# HC-SR04_v2_SCH.net
KiCad netlist of a schematic drawn in Altium Designer
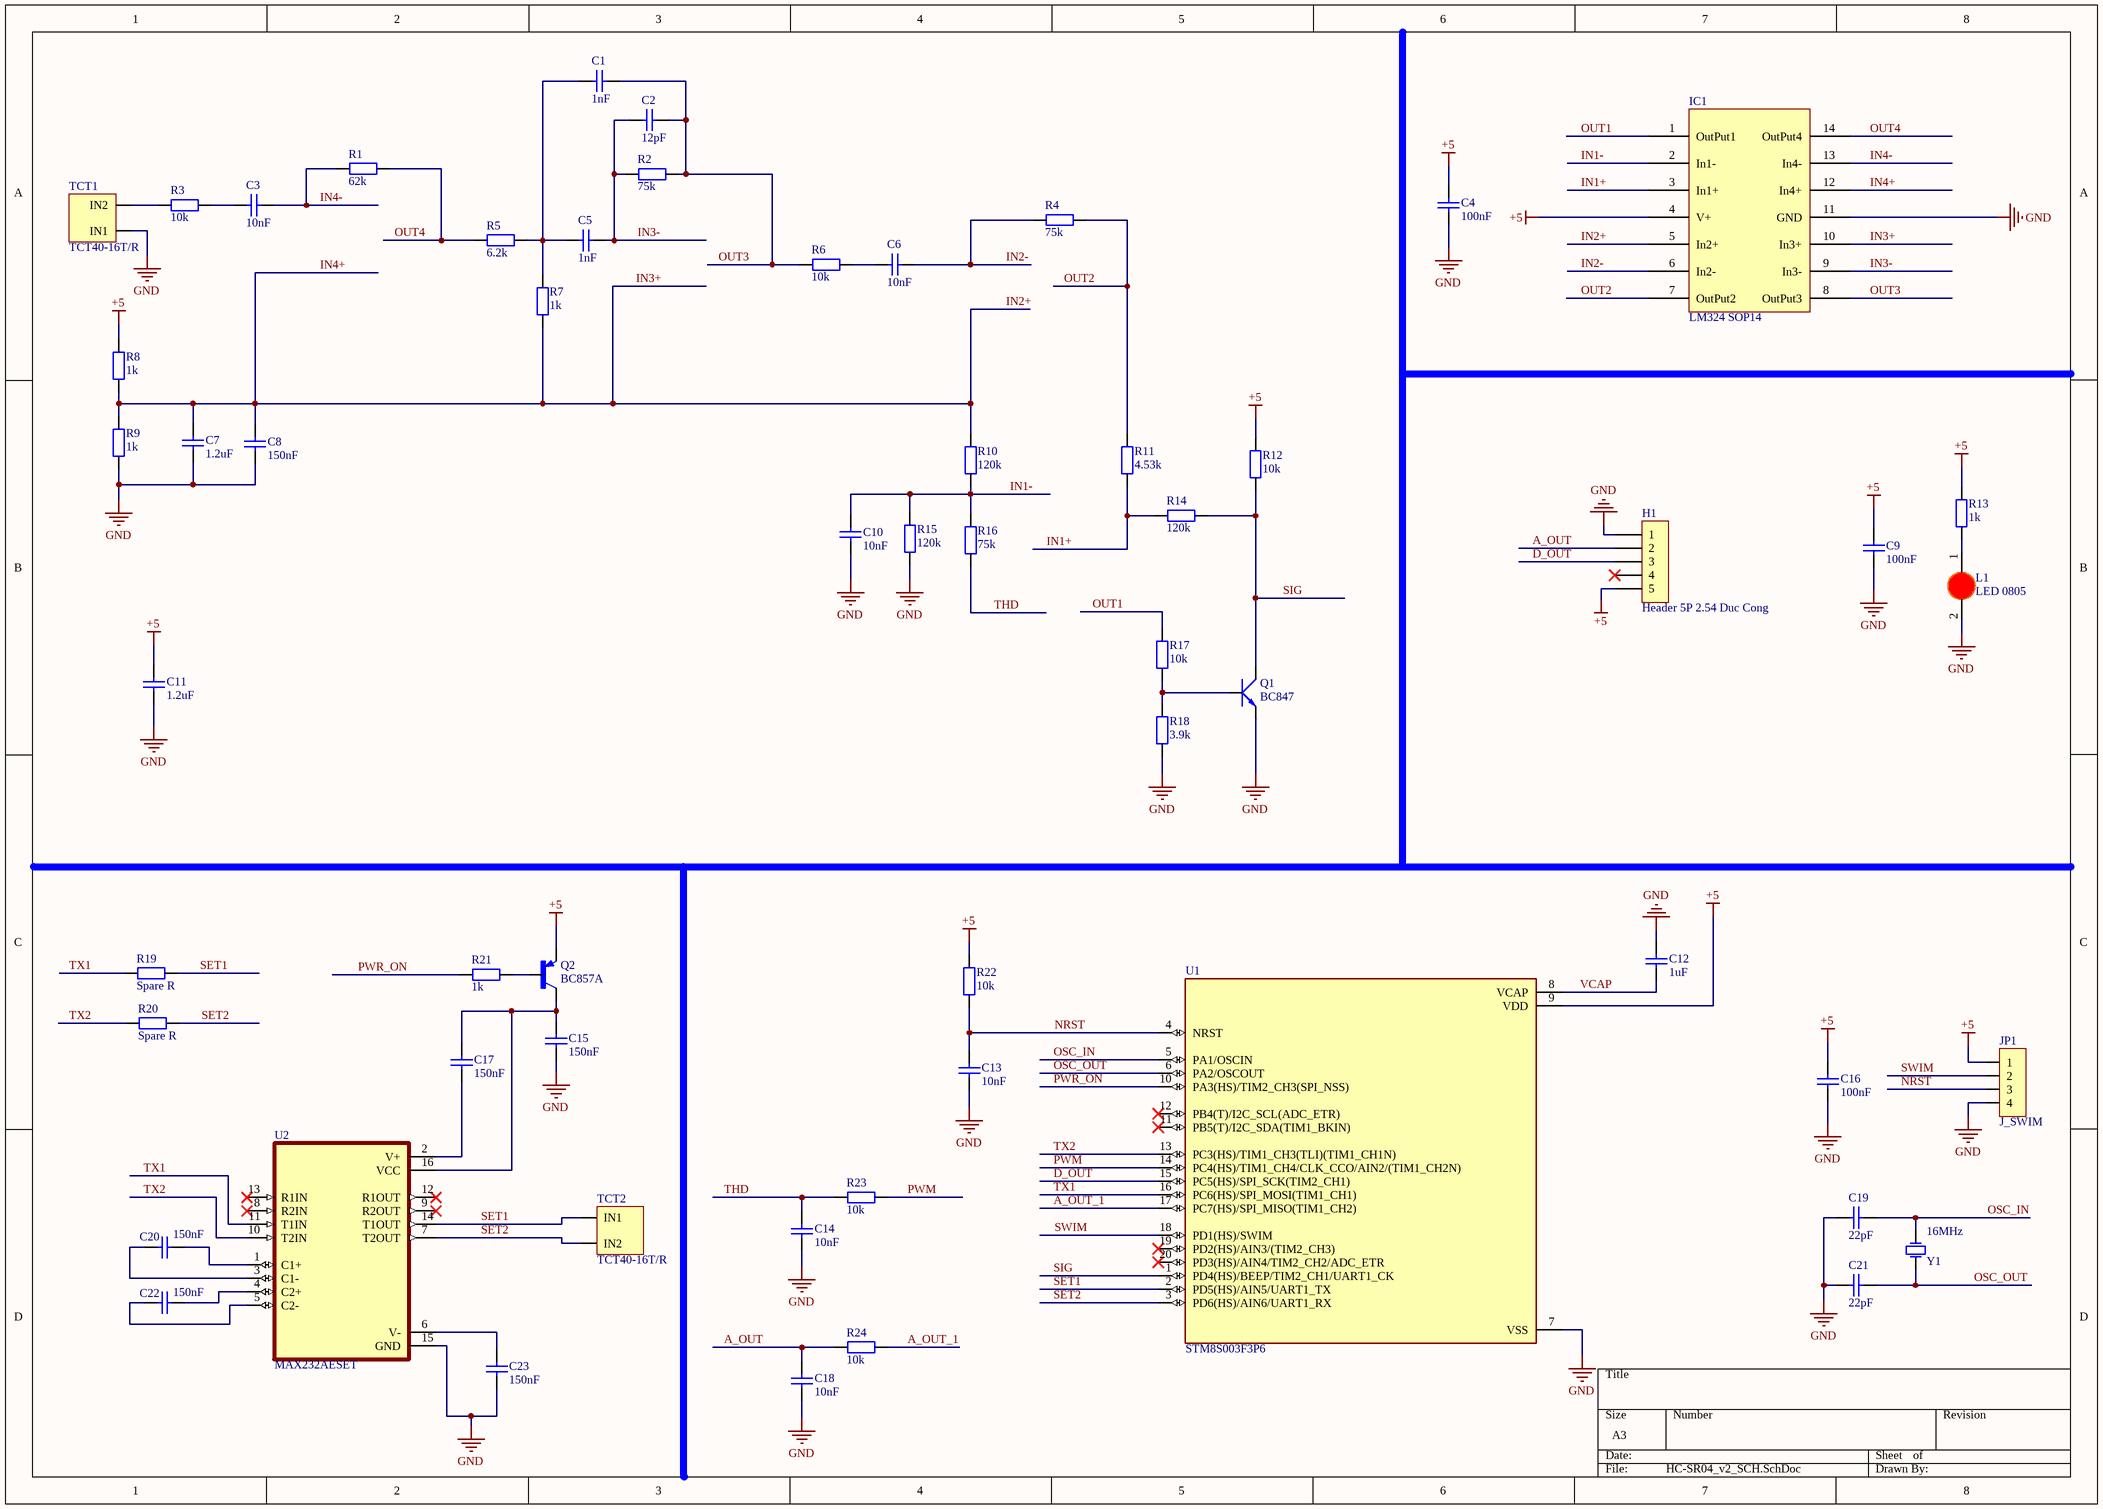
[diagram p0: HC-SR04_v2_SCH.SchDoc]

(export (version "E")
  (design (tool "Eeschema 10.0.6"))
  (components
    (comp (ref "C1")
      (value "1nF")
      (footprint "tu 0603")
      (description "Dán")
      (libsource (lib "namnt_Lib") (part "Tu 0603 102 50V 10%"))
    )
    (comp (ref "C2")
      (value "12pF")
      (footprint "tu 0603")
      (description "Dán")
      (libsource (lib "namnt_Lib") (part "Tu 0603 102 50V 10%"))
    )
    (comp (ref "C3")
      (value "10nF")
      (footprint "tu 0603")
      (description "Dán")
      (libsource (lib "namnt_Lib") (part "Tu 0603 103 50V 10%"))
    )
    (comp (ref "C4")
      (value "100nF")
      (footprint "tu 0603")
      (description "Dán")
      (libsource (lib "namnt_Lib") (part "Tu 0603 102 50V 10%"))
    )
    (comp (ref "C5")
      (value "1nF")
      (footprint "tu 0603")
      (description "Dán")
      (libsource (lib "namnt_Lib") (part "Tu 0603 102 50V 10%"))
    )
    (comp (ref "C6")
      (value "10nF")
      (footprint "tu 0603")
      (description "Dán")
      (libsource (lib "namnt_Lib") (part "Tu 0603 102 50V 10%"))
    )
    (comp (ref "C7")
      (value "1.2uF")
      (footprint "tu 0603")
      (description "Dán")
      (libsource (lib "namnt_Lib") (part "Tu 0603 104 50V 10%"))
    )
    (comp (ref "C8")
      (value "150nF")
      (footprint "tu 0603")
      (description "Dán")
      (libsource (lib "namnt_Lib") (part "Tu 0603 104 50V 10%"))
    )
    (comp (ref "C9")
      (value "100nF")
      (footprint "tu 0603")
      (description "Dán")
      (libsource (lib "namnt_Lib") (part "Tu 0603 102 50V 10%"))
    )
    (comp (ref "C10")
      (value "10nF")
      (footprint "tu 0603")
      (description "Dán")
      (libsource (lib "namnt_Lib") (part "Tu 0603 102 50V 10%"))
    )
    (comp (ref "C11")
      (value "1.2uF")
      (footprint "tu 0603")
      (description "Dán")
      (libsource (lib "namnt_Lib") (part "Tu 0603 102 50V 10%"))
    )
    (comp (ref "C12")
      (value "1uF")
      (footprint "tu 0603")
      (description "Dán")
      (libsource (lib "namnt_Lib") (part "Tu 0603 102 50V 10%"))
    )
    (comp (ref "C13")
      (value "10nF")
      (footprint "tu 0603")
      (description "Dán")
      (libsource (lib "namnt_Lib") (part "Tu 0603 102 50V 10%"))
    )
    (comp (ref "C14")
      (value "10nF")
      (footprint "tu 0603")
      (description "Dán")
      (libsource (lib "namnt_Lib") (part "Tu 0603 102 50V 10%"))
    )
    (comp (ref "C15")
      (value "150nF")
      (footprint "tu 0603")
      (description "Dán")
      (libsource (lib "namnt_Lib") (part "Tu 0603 102 50V 10%"))
    )
    (comp (ref "C16")
      (value "100nF")
      (footprint "tu 0603")
      (description "Dán")
      (libsource (lib "namnt_Lib") (part "Tu 0603 102 50V 10%"))
    )
    (comp (ref "C17")
      (value "150nF")
      (footprint "tu 0603")
      (description "Dán")
      (libsource (lib "namnt_Lib") (part "Tu 0603 102 50V 10%"))
    )
    (comp (ref "C18")
      (value "10nF")
      (footprint "tu 0603")
      (description "Dán")
      (libsource (lib "namnt_Lib") (part "Tu 0603 102 50V 10%"))
    )
    (comp (ref "C19")
      (value "22pF")
      (footprint "tu 0603")
      (description "Dán")
      (libsource (lib "namnt_Lib") (part "Tu 0603 102 50V 10%"))
    )
    (comp (ref "C20")
      (value "150nF")
      (footprint "tu 0603")
      (description "Dán")
      (libsource (lib "namnt_Lib") (part "Tu 0603 102 50V 10%"))
    )
    (comp (ref "C21")
      (value "22pF")
      (footprint "tu 0603")
      (description "Dán")
      (libsource (lib "namnt_Lib") (part "Tu 0603 102 50V 10%"))
    )
    (comp (ref "C22")
      (value "150nF")
      (footprint "tu 0603")
      (description "Dán")
      (libsource (lib "namnt_Lib") (part "Tu 0603 102 50V 10%"))
    )
    (comp (ref "C23")
      (value "150nF")
      (footprint "tu 0603")
      (description "Dán")
      (libsource (lib "namnt_Lib") (part "Tu 0603 102 50V 10%"))
    )
    (comp (ref "H1")
      (value "Header 5P 2.54 Duc Cong")
      (footprint "Header 5P DC 2.54")
      (description "Cắm")
      (libsource (lib "namnt_Lib") (part "Header 5P 2.54 Duc Cong"))
    )
    (comp (ref "IC1")
      (value "LM324 SOP14")
      (footprint "sop 14")
      (description "Dán")
      (libsource (lib "namnt_Lib") (part "LM324 SOP14"))
    )
    (comp (ref "JP1")
      (value "J_SWIM")
      (footprint "JP 1x4 DT")
      (description "Cắm")
      (libsource (lib "namnt_Lib") (part "JP 1x4 2.54 Duc Thang"))
    )
    (comp (ref "L1")
      (value "LED 0805")
      (footprint "LED-0805-Red")
      (description "Dán")
      (libsource (lib "namnt_Lib") (part "LED 0805 Do"))
    )
    (comp (ref "Q1")
      (value "BC847")
      (footprint "SOT-23")
      (description "SOT-23")
      (libsource (lib "namnt_Lib") (part "Trans BC817"))
    )
    (comp (ref "Q2")
      (value "BC857A")
      (footprint "TRANS_BC857A_RFG")
      (description "SOT-23, 200mW, PNP Bipolar Transistor")
      (fields (field (name "MF") "Taiwan Semiconductor") (field (name "MP") "BC857A RFG"))
      (libsource (lib "namnt_Lib") (part "BC857A_RFG"))
    )
    (comp (ref "R1")
      (value "62k")
      (footprint "tro smd 0603")
      (description "Dán")
      (libsource (lib "namnt_Lib") (part "Tro 0603 1% 1k"))
    )
    (comp (ref "R2")
      (value "75k")
      (footprint "tro smd 0603")
      (description "Dán")
      (libsource (lib "namnt_Lib") (part "Tro 0603 1% 1k"))
    )
    (comp (ref "R3")
      (value "10k")
      (footprint "tro smd 0603")
      (description "Dán")
      (libsource (lib "namnt_Lib") (part "Tro 0603 1% 10k"))
    )
    (comp (ref "R4")
      (value "75k")
      (footprint "tro smd 0603")
      (description "Dán")
      (libsource (lib "namnt_Lib") (part "Tro 0603 1% 1k"))
    )
    (comp (ref "R5")
      (value "6.2k")
      (footprint "tro smd 0603")
      (description "Dán")
      (libsource (lib "namnt_Lib") (part "Tro 0603 1% 1k"))
    )
    (comp (ref "R6")
      (value "10k")
      (footprint "tro smd 0603")
      (description "Dán")
      (libsource (lib "namnt_Lib") (part "Tro 0603 1% 1k"))
    )
    (comp (ref "R7")
      (value "1k")
      (footprint "tro smd 0603")
      (description "Dán")
      (libsource (lib "namnt_Lib") (part "Tro 0603 1% 1k"))
    )
    (comp (ref "R8")
      (value "1k")
      (footprint "tro smd 0603")
      (description "Dán")
      (libsource (lib "namnt_Lib") (part "Tro 0603 1% 1k"))
    )
    (comp (ref "R9")
      (value "1k")
      (footprint "tro smd 0603")
      (description "Dán")
      (libsource (lib "namnt_Lib") (part "Tro 0603 1% 1k"))
    )
    (comp (ref "R10")
      (value "120k")
      (footprint "tro smd 0603")
      (description "Dán")
      (libsource (lib "namnt_Lib") (part "Tro 0603 1% 1k"))
    )
    (comp (ref "R11")
      (value "4.53k")
      (footprint "tro smd 0603")
      (description "Dán")
      (libsource (lib "namnt_Lib") (part "Tro 0603 1% 1k"))
    )
    (comp (ref "R12")
      (value "10k")
      (footprint "tro smd 0603")
      (description "Dán")
      (libsource (lib "namnt_Lib") (part "Tro 0603 1% 1k"))
    )
    (comp (ref "R13")
      (value "1k")
      (footprint "tro smd 0603")
      (description "Dán")
      (libsource (lib "namnt_Lib") (part "Tro 0603 1% 1k"))
    )
    (comp (ref "R14")
      (value "120k")
      (footprint "tro smd 0603")
      (description "Dán")
      (libsource (lib "namnt_Lib") (part "Tro 0603 1% 1k"))
    )
    (comp (ref "R15")
      (value "120k")
      (footprint "tro smd 0603")
      (description "Dán")
      (libsource (lib "namnt_Lib") (part "Tro 0603 1% 1k"))
    )
    (comp (ref "R16")
      (value "75k")
      (footprint "tro smd 0603")
      (description "Dán")
      (libsource (lib "namnt_Lib") (part "Tro 0603 1% 1k"))
    )
    (comp (ref "R17")
      (value "10k")
      (footprint "tro smd 0603")
      (description "Dán")
      (libsource (lib "namnt_Lib") (part "Tro 0603 1% 1k"))
    )
    (comp (ref "R18")
      (value "3.9k")
      (footprint "tro smd 0603")
      (description "Dán")
      (libsource (lib "namnt_Lib") (part "Tro 0603 1% 1k"))
    )
    (comp (ref "R19")
      (value "Spare R")
      (footprint "tro smd 0603")
      (description "Dán")
      (libsource (lib "namnt_Lib") (part "Tro 0603 1% 1k"))
    )
    (comp (ref "R20")
      (value "Spare R")
      (footprint "tro smd 0603")
      (description "Dán")
      (libsource (lib "namnt_Lib") (part "Tro 0603 1% 1k"))
    )
    (comp (ref "R21")
      (value "1k")
      (footprint "tro smd 0603")
      (description "Dán")
      (libsource (lib "namnt_Lib") (part "Tro 0603 1% 1k"))
    )
    (comp (ref "R22")
      (value "10k")
      (footprint "tro smd 0603")
      (description "Dán")
      (libsource (lib "namnt_Lib") (part "Tro 0603 1% 1k"))
    )
    (comp (ref "R23")
      (value "10k")
      (footprint "tro smd 0603")
      (description "Dán")
      (libsource (lib "namnt_Lib") (part "Tro 0603 1% 1k"))
    )
    (comp (ref "R24")
      (value "10k")
      (footprint "tro smd 0603")
      (description "Dán")
      (libsource (lib "namnt_Lib") (part "Tro 0603 1% 1k"))
    )
    (comp (ref "TCT1")
      (value "TCT40-16T/R")
      (footprint "TCT40")
      (description "Piezoelectric Ceramic Ultrasonic Sensor")
      (libsource (lib "namnt_Lib") (part "TCT40-16T/R"))
    )
    (comp (ref "TCT2")
      (value "TCT40-16T/R")
      (footprint "TCT40")
      (description "Piezoelectric Ceramic Ultrasonic Sensor")
      (libsource (lib "") (part "TCT40-16T/R_1"))
    )
    (comp (ref "U1")
      (value "STM8S003F3P6")
      (footprint "SOP65P640X120-20N")
      (description "STM8 series Microcontroller IC 8-Bit 16MHz 8KB (8K x 8) FLASH 20-TSSOP")
      (fields (field (name "MF") "STMicroelectronics"))
      (libsource (lib "namnt_Lib") (part "STM8S003F3P6"))
    )
    (comp (ref "U2")
      (value "MAX232AESET")
      (footprint "SOIC127P600X175-16N")
      (description "Dual Transmitter/Receiver RS-232 16-Pin SOIC N Tube")
      (fields (field (name "MF") "Analog Devices") (field (name "MP") "MAX232AESE+"))
      (libsource (lib "namnt_Lib") (part "MAX232AESET"))
    )
    (comp (ref "Y1")
      (value "16MHz")
      (footprint "THACH ANH DAN 3215")
      (description "C700805")
      (libsource (lib "namnt_Lib") (part "Thach Anh SMD 3225"))
    )
  )
  (nets
    (net (code "1") (name "+5") (class "Default")
      (node (ref "C11") (pin "1") (pinfunction "1_1") (pintype "passive"))
      (node (ref "C16") (pin "1") (pinfunction "1_1") (pintype "passive"))
      (node (ref "C4") (pin "1") (pinfunction "1_1") (pintype "passive"))
      (node (ref "C9") (pin "1") (pinfunction "1_1") (pintype "passive"))
      (node (ref "H1") (pin "5") (pinfunction "5_5") (pintype "passive"))
      (node (ref "IC1") (pin "4") (pinfunction "V+_4") (pintype "passive"))
      (node (ref "JP1") (pin "1") (pinfunction "1_1") (pintype "passive"))
      (node (ref "Q2") (pin "2") (pinfunction "E_2") (pintype "passive"))
      (node (ref "R12") (pin "2") (pinfunction "2_2") (pintype "passive"))
      (node (ref "R13") (pin "2") (pinfunction "2_2") (pintype "passive"))
      (node (ref "R22") (pin "1") (pinfunction "1_1") (pintype "passive"))
      (node (ref "R8") (pin "2") (pinfunction "2_2") (pintype "passive"))
      (node (ref "U1") (pin "9") (pinfunction "VDD_9") (pintype "power_in"))
    )
    (net (code "2") (name "/A_OUT") (class "Default")
      (node (ref "C18") (pin "1") (pinfunction "1_1") (pintype "passive"))
      (node (ref "H1") (pin "2") (pinfunction "2_2") (pintype "passive"))
      (node (ref "R24") (pin "2") (pinfunction "2_2") (pintype "passive"))
    )
    (net (code "3") (name "/A_OUT_1") (class "Default")
      (node (ref "R24") (pin "1") (pinfunction "1_1") (pintype "passive"))
      (node (ref "U1") (pin "17") (pinfunction "PC7(HS)/SPI_MISO(TIM1_CH2)_17") (pintype "bidirectional"))
    )
    (net (code "4") (name "/D_OUT") (class "Default")
      (node (ref "H1") (pin "3") (pinfunction "3_3") (pintype "passive"))
      (node (ref "U1") (pin "15") (pinfunction "PC5(HS)/SPI_SCK(TIM2_CH1)_15") (pintype "bidirectional"))
    )
    (net (code "5") (name "/IN1+") (class "Default")
      (node (ref "IC1") (pin "3") (pinfunction "In1+_3") (pintype "passive"))
      (node (ref "R11") (pin "2") (pinfunction "2_2") (pintype "passive"))
      (node (ref "R14") (pin "1") (pinfunction "1_1") (pintype "passive"))
    )
    (net (code "6") (name "/IN1-") (class "Default")
      (node (ref "C10") (pin "1") (pinfunction "1_1") (pintype "passive"))
      (node (ref "IC1") (pin "2") (pinfunction "In1-_2") (pintype "passive"))
      (node (ref "R10") (pin "2") (pinfunction "2_2") (pintype "passive"))
      (node (ref "R15") (pin "2") (pinfunction "2_2") (pintype "passive"))
      (node (ref "R16") (pin "2") (pinfunction "2_2") (pintype "passive"))
    )
    (net (code "7") (name "/IN2+") (class "Default")
      (node (ref "C7") (pin "1") (pinfunction "1_1") (pintype "passive"))
      (node (ref "C8") (pin "1") (pinfunction "1_1") (pintype "passive"))
      (node (ref "IC1") (pin "10") (pinfunction "In3+_10") (pintype "passive"))
      (node (ref "IC1") (pin "12") (pinfunction "In4+_12") (pintype "passive"))
      (node (ref "IC1") (pin "5") (pinfunction "In2+_5") (pintype "passive"))
      (node (ref "R10") (pin "1") (pinfunction "1_1") (pintype "passive"))
      (node (ref "R7") (pin "2") (pinfunction "2_2") (pintype "passive"))
      (node (ref "R8") (pin "1") (pinfunction "1_1") (pintype "passive"))
      (node (ref "R9") (pin "2") (pinfunction "2_2") (pintype "passive"))
    )
    (net (code "8") (name "/IN2-") (class "Default")
      (node (ref "C6") (pin "1") (pinfunction "1_1") (pintype "passive"))
      (node (ref "IC1") (pin "6") (pinfunction "In2-_6") (pintype "passive"))
      (node (ref "R4") (pin "2") (pinfunction "2_2") (pintype "passive"))
    )
    (net (code "9") (name "/IN3-") (class "Default")
      (node (ref "C2") (pin "2") (pinfunction "2_2") (pintype "passive"))
      (node (ref "C5") (pin "1") (pinfunction "1_1") (pintype "passive"))
      (node (ref "IC1") (pin "9") (pinfunction "In3-_9") (pintype "passive"))
      (node (ref "R2") (pin "2") (pinfunction "2_2") (pintype "passive"))
    )
    (net (code "10") (name "/IN4-") (class "Default")
      (node (ref "C3") (pin "2") (pinfunction "2_2") (pintype "passive"))
      (node (ref "IC1") (pin "13") (pinfunction "In4-_13") (pintype "passive"))
      (node (ref "R1") (pin "2") (pinfunction "2_2") (pintype "passive"))
    )
    (net (code "11") (name "/NRST") (class "Default")
      (node (ref "C13") (pin "1") (pinfunction "1_1") (pintype "passive"))
      (node (ref "JP1") (pin "3") (pinfunction "3_3") (pintype "passive"))
      (node (ref "R22") (pin "2") (pinfunction "2_2") (pintype "passive"))
      (node (ref "U1") (pin "4") (pinfunction "NRST_4") (pintype "bidirectional"))
    )
    (net (code "12") (name "/OSC_IN") (class "Default")
      (node (ref "C19") (pin "2") (pinfunction "2_2") (pintype "passive"))
      (node (ref "U1") (pin "5") (pinfunction "PA1/OSCIN_5") (pintype "bidirectional"))
      (node (ref "Y1") (pin "2") (pinfunction "OSC2_2") (pintype "passive"))
    )
    (net (code "13") (name "/OSC_OUT") (class "Default")
      (node (ref "C21") (pin "2") (pinfunction "2_2") (pintype "passive"))
      (node (ref "U1") (pin "6") (pinfunction "PA2/OSCOUT_6") (pintype "bidirectional"))
      (node (ref "Y1") (pin "1") (pinfunction "OSC1_1") (pintype "passive"))
    )
    (net (code "14") (name "/OUT1") (class "Default")
      (node (ref "IC1") (pin "1") (pinfunction "OutPut1_1") (pintype "passive"))
      (node (ref "R17") (pin "2") (pinfunction "2_2") (pintype "passive"))
    )
    (net (code "15") (name "/OUT2") (class "Default")
      (node (ref "IC1") (pin "7") (pinfunction "OutPut2_7") (pintype "passive"))
      (node (ref "R11") (pin "1") (pinfunction "1_1") (pintype "passive"))
      (node (ref "R4") (pin "1") (pinfunction "1_1") (pintype "passive"))
    )
    (net (code "16") (name "/OUT3") (class "Default")
      (node (ref "C1") (pin "1") (pinfunction "1_1") (pintype "passive"))
      (node (ref "C2") (pin "1") (pinfunction "1_1") (pintype "passive"))
      (node (ref "IC1") (pin "8") (pinfunction "OutPut3_8") (pintype "passive"))
      (node (ref "R2") (pin "1") (pinfunction "1_1") (pintype "passive"))
      (node (ref "R6") (pin "2") (pinfunction "2_2") (pintype "passive"))
    )
    (net (code "17") (name "/OUT4") (class "Default")
      (node (ref "IC1") (pin "14") (pinfunction "OutPut4_14") (pintype "passive"))
      (node (ref "R1") (pin "1") (pinfunction "1_1") (pintype "passive"))
      (node (ref "R5") (pin "2") (pinfunction "2_2") (pintype "passive"))
    )
    (net (code "18") (name "/PWM") (class "Default")
      (node (ref "R23") (pin "1") (pinfunction "1_1") (pintype "passive"))
      (node (ref "U1") (pin "14") (pinfunction "PC4(HS)/TIM1_CH4/CLK_CCO/AIN2/(TIM1_CH2N)_14") (pintype "bidirectional"))
    )
    (net (code "19") (name "/PWR_ON") (class "Default")
      (node (ref "R21") (pin "2") (pinfunction "2_2") (pintype "passive"))
      (node (ref "U1") (pin "10") (pinfunction "PA3(HS)/TIM2_CH3(SPI_NSS)_10") (pintype "bidirectional"))
    )
    (net (code "20") (name "/SET1") (class "Default")
      (node (ref "R19") (pin "2") (pinfunction "2_2") (pintype "passive"))
      (node (ref "TCT2") (pin "1") (pinfunction "IN1_1") (pintype "passive"))
      (node (ref "U1") (pin "2") (pinfunction "PD5(HS)/AIN5/UART1_TX_2") (pintype "bidirectional"))
      (node (ref "U2") (pin "14") (pinfunction "T1OUT_14") (pintype "output"))
    )
    (net (code "21") (name "/SET2") (class "Default")
      (node (ref "R20") (pin "2") (pinfunction "2_2") (pintype "passive"))
      (node (ref "TCT2") (pin "2") (pinfunction "IN2_2") (pintype "passive"))
      (node (ref "U1") (pin "3") (pinfunction "PD6(HS)/AIN6/UART1_RX_3") (pintype "bidirectional"))
      (node (ref "U2") (pin "7") (pinfunction "T2OUT_7") (pintype "output"))
    )
    (net (code "22") (name "/SIG") (class "Default")
      (node (ref "Q1") (pin "3") (pinfunction "C_3") (pintype "passive"))
      (node (ref "R12") (pin "1") (pinfunction "1_1") (pintype "passive"))
      (node (ref "R14") (pin "2") (pinfunction "2_2") (pintype "passive"))
      (node (ref "U1") (pin "1") (pinfunction "PD4(HS)/BEEP/TIM2_CH1/UART1_CK_1") (pintype "bidirectional"))
    )
    (net (code "23") (name "/SWIM") (class "Default")
      (node (ref "JP1") (pin "2") (pinfunction "2_2") (pintype "passive"))
      (node (ref "U1") (pin "18") (pinfunction "PD1(HS)/SWIM_18") (pintype "bidirectional"))
    )
    (net (code "24") (name "/THD") (class "Default")
      (node (ref "C14") (pin "1") (pinfunction "1_1") (pintype "passive"))
      (node (ref "R16") (pin "1") (pinfunction "1_1") (pintype "passive"))
      (node (ref "R23") (pin "2") (pinfunction "2_2") (pintype "passive"))
    )
    (net (code "25") (name "/TX1") (class "Default")
      (node (ref "R19") (pin "1") (pinfunction "1_1") (pintype "passive"))
      (node (ref "U1") (pin "16") (pinfunction "PC6(HS)/SPI_MOSI(TIM1_CH1)_16") (pintype "bidirectional"))
      (node (ref "U2") (pin "11") (pinfunction "T1IN_11") (pintype "input"))
    )
    (net (code "26") (name "/TX2") (class "Default")
      (node (ref "R20") (pin "1") (pinfunction "1_1") (pintype "passive"))
      (node (ref "U1") (pin "13") (pinfunction "PC3(HS)/TIM1_CH3(TLI)(TIM1_CH1N)_13") (pintype "bidirectional"))
      (node (ref "U2") (pin "10") (pinfunction "T2IN_10") (pintype "input"))
    )
    (net (code "27") (name "/VCAP") (class "Default")
      (node (ref "C12") (pin "2") (pinfunction "2_2") (pintype "passive"))
      (node (ref "U1") (pin "8") (pinfunction "VCAP_8") (pintype "power_in"))
    )
    (net (code "28") (name "GND") (class "Default")
      (node (ref "C10") (pin "2") (pinfunction "2_2") (pintype "passive"))
      (node (ref "C11") (pin "2") (pinfunction "2_2") (pintype "passive"))
      (node (ref "C12") (pin "1") (pinfunction "1_1") (pintype "passive"))
      (node (ref "C13") (pin "2") (pinfunction "2_2") (pintype "passive"))
      (node (ref "C14") (pin "2") (pinfunction "2_2") (pintype "passive"))
      (node (ref "C15") (pin "2") (pinfunction "2_2") (pintype "passive"))
      (node (ref "C16") (pin "2") (pinfunction "2_2") (pintype "passive"))
      (node (ref "C18") (pin "2") (pinfunction "2_2") (pintype "passive"))
      (node (ref "C19") (pin "1") (pinfunction "1_1") (pintype "passive"))
      (node (ref "C21") (pin "1") (pinfunction "1_1") (pintype "passive"))
      (node (ref "C23") (pin "2") (pinfunction "2_2") (pintype "passive"))
      (node (ref "C4") (pin "2") (pinfunction "2_2") (pintype "passive"))
      (node (ref "C7") (pin "2") (pinfunction "2_2") (pintype "passive"))
      (node (ref "C8") (pin "2") (pinfunction "2_2") (pintype "passive"))
      (node (ref "C9") (pin "2") (pinfunction "2_2") (pintype "passive"))
      (node (ref "H1") (pin "1") (pinfunction "1_1") (pintype "passive"))
      (node (ref "IC1") (pin "11") (pinfunction "GND_11") (pintype "passive"))
      (node (ref "JP1") (pin "4") (pinfunction "4_4") (pintype "passive"))
      (node (ref "L1") (pin "2") (pinfunction "K_2") (pintype "passive"))
      (node (ref "Q1") (pin "2") (pinfunction "E_2") (pintype "passive"))
      (node (ref "R15") (pin "1") (pinfunction "1_1") (pintype "passive"))
      (node (ref "R18") (pin "1") (pinfunction "1_1") (pintype "passive"))
      (node (ref "R9") (pin "1") (pinfunction "1_1") (pintype "passive"))
      (node (ref "TCT1") (pin "1") (pinfunction "IN1_1") (pintype "passive"))
      (node (ref "U1") (pin "7") (pinfunction "VSS_7") (pintype "power_in"))
      (node (ref "U2") (pin "15") (pinfunction "GND_15") (pintype "power_in"))
    )
    (net (code "29") (name "Net-(C1-Pad2)") (class "Default")
      (node (ref "C1") (pin "2") (pinfunction "2_2") (pintype "passive"))
      (node (ref "C5") (pin "2") (pinfunction "2_2") (pintype "passive"))
      (node (ref "R5") (pin "1") (pinfunction "1_1") (pintype "passive"))
      (node (ref "R7") (pin "1") (pinfunction "1_1") (pintype "passive"))
    )
    (net (code "30") (name "Net-(C3-Pad1)") (class "Default")
      (node (ref "C3") (pin "1") (pinfunction "1_1") (pintype "passive"))
      (node (ref "R3") (pin "2") (pinfunction "2_2") (pintype "passive"))
    )
    (net (code "31") (name "Net-(C6-Pad2)") (class "Default")
      (node (ref "C6") (pin "2") (pinfunction "2_2") (pintype "passive"))
      (node (ref "R6") (pin "1") (pinfunction "1_1") (pintype "passive"))
    )
    (net (code "32") (name "Net-(L1-A)") (class "Default")
      (node (ref "L1") (pin "1") (pinfunction "A_1") (pintype "passive"))
      (node (ref "R13") (pin "1") (pinfunction "1_1") (pintype "passive"))
    )
    (net (code "33") (name "Net-(Q1-B)") (class "Default")
      (node (ref "Q1") (pin "1") (pinfunction "B_1") (pintype "passive"))
      (node (ref "R17") (pin "1") (pinfunction "1_1") (pintype "passive"))
      (node (ref "R18") (pin "2") (pinfunction "2_2") (pintype "passive"))
    )
    (net (code "34") (name "Net-(Q2-B)") (class "Default")
      (node (ref "Q2") (pin "1") (pinfunction "B_1") (pintype "passive"))
      (node (ref "R21") (pin "1") (pinfunction "1_1") (pintype "passive"))
    )
    (net (code "35") (name "Net-(Q2-C)") (class "Default")
      (node (ref "C15") (pin "1") (pinfunction "1_1") (pintype "passive"))
      (node (ref "C17") (pin "1") (pinfunction "1_1") (pintype "passive"))
      (node (ref "Q2") (pin "3") (pinfunction "C_3") (pintype "passive"))
      (node (ref "U2") (pin "16") (pinfunction "VCC_16") (pintype "power_in"))
    )
    (net (code "36") (name "Net-(TCT1-IN2)") (class "Default")
      (node (ref "R3") (pin "1") (pinfunction "1_1") (pintype "passive"))
      (node (ref "TCT1") (pin "2") (pinfunction "IN2_2") (pintype "passive"))
    )
    (net (code "37") (name "Net-(U2-C1+)") (class "Default")
      (node (ref "C20") (pin "2") (pinfunction "2_2") (pintype "passive"))
      (node (ref "U2") (pin "1") (pinfunction "C1+_1") (pintype "bidirectional"))
    )
    (net (code "38") (name "Net-(U2-C1-)") (class "Default")
      (node (ref "C20") (pin "1") (pinfunction "1_1") (pintype "passive"))
      (node (ref "U2") (pin "3") (pinfunction "C1-_3") (pintype "bidirectional"))
    )
    (net (code "39") (name "Net-(U2-C2+)") (class "Default")
      (node (ref "C22") (pin "2") (pinfunction "2_2") (pintype "passive"))
      (node (ref "U2") (pin "4") (pinfunction "C2+_4") (pintype "bidirectional"))
    )
    (net (code "40") (name "Net-(U2-C2-)") (class "Default")
      (node (ref "C22") (pin "1") (pinfunction "1_1") (pintype "passive"))
      (node (ref "U2") (pin "5") (pinfunction "C2-_5") (pintype "bidirectional"))
    )
    (net (code "41") (name "Net-(U2-V+)") (class "Default")
      (node (ref "C17") (pin "2") (pinfunction "2_2") (pintype "passive"))
      (node (ref "U2") (pin "2") (pinfunction "V+_2") (pintype "power_in"))
    )
    (net (code "42") (name "Net-(U2-V-)") (class "Default")
      (node (ref "C23") (pin "1") (pinfunction "1_1") (pintype "passive"))
      (node (ref "U2") (pin "6") (pinfunction "V-_6") (pintype "power_in"))
    )
    (net (code "43") (name "unconnected-(H1-Pad4)") (class "Default")
      (node (ref "H1") (pin "4") (pinfunction "4_4") (pintype "passive+no_connect"))
    )
    (net (code "44") (name "unconnected-(U1-PB4(T){slash}I2C_SCL(ADC_ETR)-Pad12)") (class "Default")
      (node (ref "U1") (pin "12") (pinfunction "PB4(T)/I2C_SCL(ADC_ETR)_12") (pintype "bidirectional+no_connect"))
    )
    (net (code "45") (name "unconnected-(U1-PB5(T){slash}I2C_SDA(TIM1_BKIN)-Pad11)") (class "Default")
      (node (ref "U1") (pin "11") (pinfunction "PB5(T)/I2C_SDA(TIM1_BKIN)_11") (pintype "bidirectional+no_connect"))
    )
    (net (code "46") (name "unconnected-(U1-PD2(HS){slash}AIN3{slash}(TIM2_CH3)-Pad19)") (class "Default")
      (node (ref "U1") (pin "19") (pinfunction "PD2(HS)/AIN3/(TIM2_CH3)_19") (pintype "bidirectional+no_connect"))
    )
    (net (code "47") (name "unconnected-(U1-PD3(HS){slash}AIN4{slash}TIM2_CH2{slash}ADC_ETR-Pad20)") (class "Default")
      (node (ref "U1") (pin "20") (pinfunction "PD3(HS)/AIN4/TIM2_CH2/ADC_ETR_20") (pintype "bidirectional+no_connect"))
    )
    (net (code "48") (name "unconnected-(U2-R1IN-Pad13)") (class "Default")
      (node (ref "U2") (pin "13") (pinfunction "R1IN_13") (pintype "input+no_connect"))
    )
    (net (code "49") (name "unconnected-(U2-R1OUT-Pad12)") (class "Default")
      (node (ref "U2") (pin "12") (pinfunction "R1OUT_12") (pintype "output+no_connect"))
    )
    (net (code "50") (name "unconnected-(U2-R2IN-Pad8)") (class "Default")
      (node (ref "U2") (pin "8") (pinfunction "R2IN_8") (pintype "input+no_connect"))
    )
    (net (code "51") (name "unconnected-(U2-R2OUT-Pad9)") (class "Default")
      (node (ref "U2") (pin "9") (pinfunction "R2OUT_9") (pintype "output+no_connect"))
    )
  )
)
